# 06_ETHERNET.net
KiCad netlist of a schematic drawn in Altium Designer
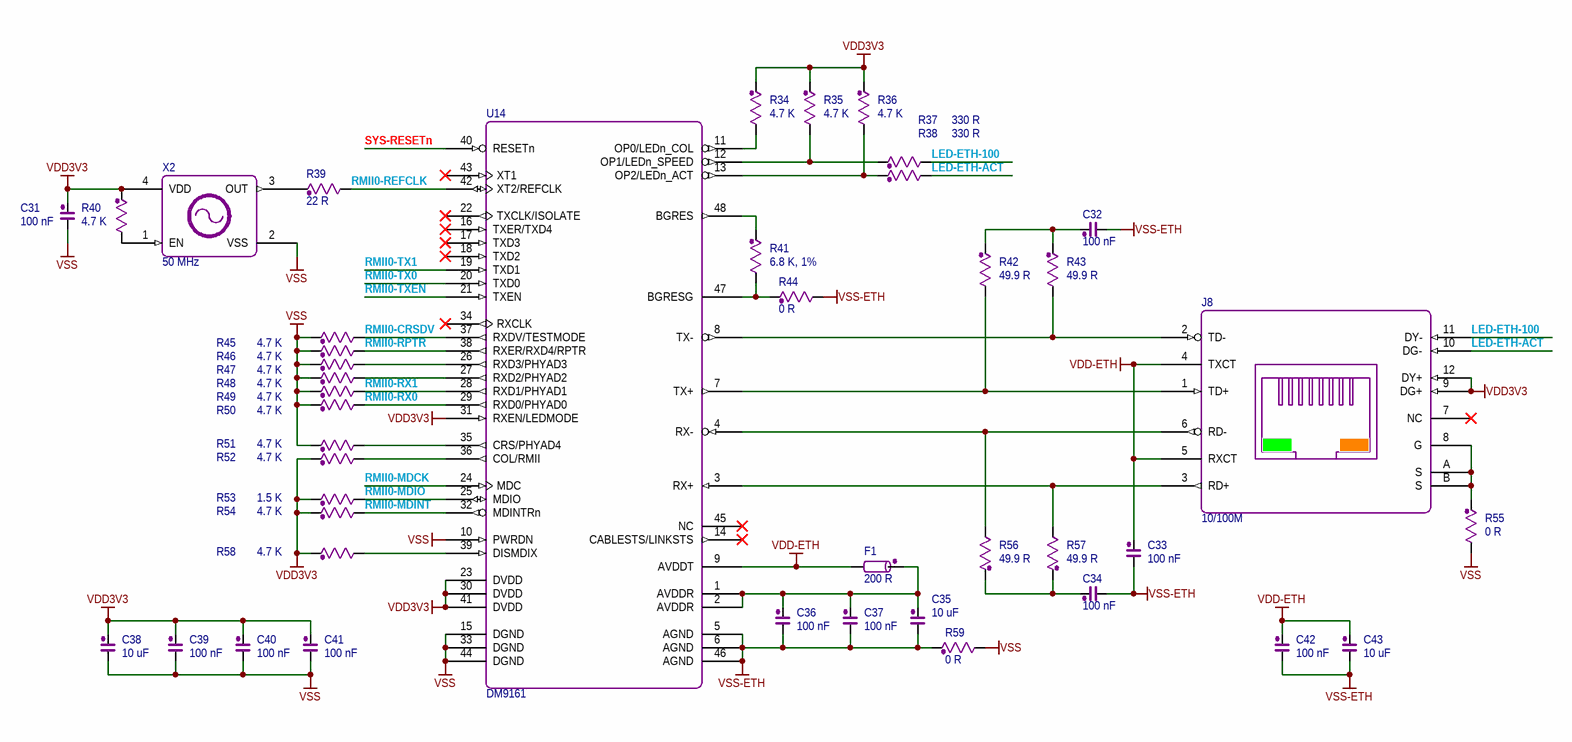
[diagram p0: 06_ETHERNET.SchDoc]

(export (version "E")
  (design (tool "Eeschema 10.0.6"))
  (components
    (comp (ref "C31")
      (value "100 nF")
      (footprint "0402A1")
      (description "Normal Capacitor")
      (fields
        (field (name "PARTNUMBER") "0")
        (field (name "PUBLISHER") "Cowin")
        (field (name "DESIGNER") "shyul")
      )
      (libsource (lib "Basc_1_Passive") (part "CAP"))
    )
    (comp (ref "C32")
      (value "100 nF")
      (footprint "0603A1")
      (description "Normal Capacitor")
      (fields
        (field (name "PARTNUMBER") "0")
        (field (name "PUBLISHER") "Cowin")
        (field (name "DESIGNER") "shyul")
      )
      (libsource (lib "") (part "CAP_1"))
    )
    (comp (ref "C33")
      (value "100 nF")
      (footprint "0603A1")
      (description "Normal Capacitor")
      (fields
        (field (name "PARTNUMBER") "0")
        (field (name "PUBLISHER") "Cowin")
        (field (name "DESIGNER") "shyul")
      )
      (libsource (lib "Basc_1_Passive") (part "CAP"))
    )
    (comp (ref "C34")
      (value "100 nF")
      (footprint "0603A1")
      (description "Normal Capacitor")
      (fields
        (field (name "PARTNUMBER") "0")
        (field (name "PUBLISHER") "Cowin")
        (field (name "DESIGNER") "shyul")
      )
      (libsource (lib "") (part "CAP_1"))
    )
    (comp (ref "C35")
      (value "10 uF")
      (footprint "0603A1")
      (description "Normal Capacitor")
      (fields
        (field (name "PARTNUMBER") "0")
        (field (name "PUBLISHER") "Cowin")
        (field (name "DESIGNER") "shyul")
      )
      (libsource (lib "Basc_1_Passive") (part "CAP"))
    )
    (comp (ref "C36")
      (value "100 nF")
      (footprint "0402A1")
      (description "Normal Capacitor")
      (fields
        (field (name "PARTNUMBER") "0")
        (field (name "PUBLISHER") "Cowin")
        (field (name "DESIGNER") "shyul")
      )
      (libsource (lib "Basc_1_Passive") (part "CAP"))
    )
    (comp (ref "C37")
      (value "100 nF")
      (footprint "0402A1")
      (description "Normal Capacitor")
      (fields
        (field (name "PARTNUMBER") "0")
        (field (name "PUBLISHER") "Cowin")
        (field (name "DESIGNER") "shyul")
      )
      (libsource (lib "Basc_1_Passive") (part "CAP"))
    )
    (comp (ref "C38")
      (value "10 uF")
      (footprint "0603A1")
      (description "Normal Capacitor")
      (fields
        (field (name "PARTNUMBER") "0")
        (field (name "PUBLISHER") "Cowin")
        (field (name "DESIGNER") "shyul")
      )
      (libsource (lib "Basc_1_Passive") (part "CAP"))
    )
    (comp (ref "C39")
      (value "100 nF")
      (footprint "0402A1")
      (description "Normal Capacitor")
      (fields
        (field (name "PARTNUMBER") "0")
        (field (name "PUBLISHER") "Cowin")
        (field (name "DESIGNER") "shyul")
      )
      (libsource (lib "Basc_1_Passive") (part "CAP"))
    )
    (comp (ref "C40")
      (value "100 nF")
      (footprint "0402A1")
      (description "Normal Capacitor")
      (fields
        (field (name "PARTNUMBER") "0")
        (field (name "PUBLISHER") "Cowin")
        (field (name "DESIGNER") "shyul")
      )
      (libsource (lib "Basc_1_Passive") (part "CAP"))
    )
    (comp (ref "C41")
      (value "100 nF")
      (footprint "0402A1")
      (description "Normal Capacitor")
      (fields
        (field (name "PARTNUMBER") "0")
        (field (name "PUBLISHER") "Cowin")
        (field (name "DESIGNER") "shyul")
      )
      (libsource (lib "Basc_1_Passive") (part "CAP"))
    )
    (comp (ref "C42")
      (value "100 nF")
      (footprint "0402A1")
      (description "Normal Capacitor")
      (fields
        (field (name "PARTNUMBER") "0")
        (field (name "PUBLISHER") "Cowin")
        (field (name "DESIGNER") "shyul")
      )
      (libsource (lib "Basc_1_Passive") (part "CAP"))
    )
    (comp (ref "C43")
      (value "10 uF")
      (footprint "0603A1")
      (description "Normal Capacitor")
      (fields
        (field (name "PARTNUMBER") "0")
        (field (name "PUBLISHER") "Cowin")
        (field (name "DESIGNER") "shyul")
      )
      (libsource (lib "Basc_1_Passive") (part "CAP"))
    )
    (comp (ref "F1")
      (value "200 R")
      (footprint "0603A3")
      (description "EMI Bead")
      (fields
        (field (name "PARTNUMBER") "BLM")
        (field (name "DESIGNER") "shyul")
        (field (name "PUBLISHER") "Cowin")
      )
      (libsource (lib "Basc_2_EMI_Protection") (part "BEAD"))
    )
    (comp (ref "J8")
      (value "10/100M")
      (footprint "RJ45_JACK_B")
      (description "RJ45 Pulse Jack with LED")
      (fields
        (field (name "PARTNUMBER") "J0011D21B")
        (field (name "PUBLISHER") "Cowin")
        (field (name "DESIGNER") "shyul")
      )
      (libsource (lib "Connector_1_General") (part "RJ45_JACK_B"))
    )
    (comp (ref "R34")
      (value "4.7 K")
      (footprint "0402A2")
      (description "Normal Resistor")
      (fields
        (field (name "PARTNUMBER") "0")
        (field (name "DESIGNER") "shyul")
        (field (name "PUBLISHER") "Cowin")
      )
      (libsource (lib "Basc_1_Passive") (part "RES"))
    )
    (comp (ref "R35")
      (value "4.7 K")
      (footprint "0402A2")
      (description "Normal Resistor")
      (fields
        (field (name "PARTNUMBER") "0")
        (field (name "DESIGNER") "shyul")
        (field (name "PUBLISHER") "Cowin")
      )
      (libsource (lib "Basc_1_Passive") (part "RES"))
    )
    (comp (ref "R36")
      (value "4.7 K")
      (footprint "0402A2")
      (description "Normal Resistor")
      (fields
        (field (name "PARTNUMBER") "0")
        (field (name "DESIGNER") "shyul")
        (field (name "PUBLISHER") "Cowin")
      )
      (libsource (lib "Basc_1_Passive") (part "RES"))
    )
    (comp (ref "R37")
      (value "330 R")
      (footprint "0402A2")
      (description "Normal Resistor")
      (fields
        (field (name "PARTNUMBER") "0")
        (field (name "DESIGNER") "shyul")
        (field (name "PUBLISHER") "Cowin")
      )
      (libsource (lib "Basc_1_Passive") (part "RES"))
    )
    (comp (ref "R38")
      (value "330 R")
      (footprint "0402A2")
      (description "Normal Resistor")
      (fields
        (field (name "PARTNUMBER") "0")
        (field (name "DESIGNER") "shyul")
        (field (name "PUBLISHER") "Cowin")
      )
      (libsource (lib "Basc_1_Passive") (part "RES"))
    )
    (comp (ref "R39")
      (value "22 R")
      (footprint "0402A2")
      (description "Normal Resistor")
      (fields
        (field (name "PARTNUMBER") "0")
        (field (name "DESIGNER") "shyul")
        (field (name "PUBLISHER") "Cowin")
      )
      (libsource (lib "Basc_1_Passive") (part "RES"))
    )
    (comp (ref "R40")
      (value "4.7 K")
      (footprint "0402A2")
      (description "Normal Resistor")
      (fields
        (field (name "PARTNUMBER") "0")
        (field (name "DESIGNER") "shyul")
        (field (name "PUBLISHER") "Cowin")
      )
      (libsource (lib "Basc_1_Passive") (part "RES"))
    )
    (comp (ref "R41")
      (value "6.8 K, 1%")
      (footprint "0603A2")
      (description "Normal Resistor")
      (fields
        (field (name "PARTNUMBER") "0")
        (field (name "DESIGNER") "shyul")
        (field (name "PUBLISHER") "Cowin")
      )
      (libsource (lib "Basc_1_Passive") (part "RES"))
    )
    (comp (ref "R42")
      (value "49.9 R")
      (footprint "0603A2")
      (description "Normal Resistor")
      (fields
        (field (name "PARTNUMBER") "0")
        (field (name "DESIGNER") "shyul")
        (field (name "PUBLISHER") "Cowin")
      )
      (libsource (lib "Basc_1_Passive") (part "RES"))
    )
    (comp (ref "R43")
      (value "49.9 R")
      (footprint "0603A2")
      (description "Normal Resistor")
      (fields
        (field (name "PARTNUMBER") "0")
        (field (name "DESIGNER") "shyul")
        (field (name "PUBLISHER") "Cowin")
      )
      (libsource (lib "Basc_1_Passive") (part "RES"))
    )
    (comp (ref "R44")
      (value "0 R")
      (footprint "0402A2")
      (description "Normal Resistor")
      (fields
        (field (name "PARTNUMBER") "0")
        (field (name "DESIGNER") "shyul")
        (field (name "PUBLISHER") "Cowin")
      )
      (libsource (lib "Basc_1_Passive") (part "RES"))
    )
    (comp (ref "R45")
      (value "4.7 K")
      (footprint "0402A2")
      (description "Normal Resistor")
      (fields
        (field (name "PARTNUMBER") "0")
        (field (name "DESIGNER") "shyul")
        (field (name "PUBLISHER") "Cowin")
      )
      (libsource (lib "Basc_1_Passive") (part "RES"))
    )
    (comp (ref "R46")
      (value "4.7 K")
      (footprint "0402A2")
      (description "Normal Resistor")
      (fields
        (field (name "PARTNUMBER") "0")
        (field (name "DESIGNER") "shyul")
        (field (name "PUBLISHER") "Cowin")
      )
      (libsource (lib "Basc_1_Passive") (part "RES"))
    )
    (comp (ref "R47")
      (value "4.7 K")
      (footprint "0402A2")
      (description "Normal Resistor")
      (fields
        (field (name "PARTNUMBER") "0")
        (field (name "DESIGNER") "shyul")
        (field (name "PUBLISHER") "Cowin")
      )
      (libsource (lib "Basc_1_Passive") (part "RES"))
    )
    (comp (ref "R48")
      (value "4.7 K")
      (footprint "0402A2")
      (description "Normal Resistor")
      (fields
        (field (name "PARTNUMBER") "0")
        (field (name "DESIGNER") "shyul")
        (field (name "PUBLISHER") "Cowin")
      )
      (libsource (lib "Basc_1_Passive") (part "RES"))
    )
    (comp (ref "R49")
      (value "4.7 K")
      (footprint "0402A2")
      (description "Normal Resistor")
      (fields
        (field (name "PARTNUMBER") "0")
        (field (name "DESIGNER") "shyul")
        (field (name "PUBLISHER") "Cowin")
      )
      (libsource (lib "Basc_1_Passive") (part "RES"))
    )
    (comp (ref "R50")
      (value "4.7 K")
      (footprint "0402A2")
      (description "Normal Resistor")
      (fields
        (field (name "PARTNUMBER") "0")
        (field (name "DESIGNER") "shyul")
        (field (name "PUBLISHER") "Cowin")
      )
      (libsource (lib "Basc_1_Passive") (part "RES"))
    )
    (comp (ref "R51")
      (value "4.7 K")
      (footprint "0402A2")
      (description "Normal Resistor")
      (fields
        (field (name "PARTNUMBER") "0")
        (field (name "DESIGNER") "shyul")
        (field (name "PUBLISHER") "Cowin")
      )
      (libsource (lib "Basc_1_Passive") (part "RES"))
    )
    (comp (ref "R52")
      (value "4.7 K")
      (footprint "0402A2")
      (description "Normal Resistor")
      (fields
        (field (name "PARTNUMBER") "0")
        (field (name "DESIGNER") "shyul")
        (field (name "PUBLISHER") "Cowin")
      )
      (libsource (lib "Basc_1_Passive") (part "RES"))
    )
    (comp (ref "R53")
      (value "1.5 K")
      (footprint "0402A2")
      (description "Normal Resistor")
      (fields
        (field (name "PARTNUMBER") "0")
        (field (name "DESIGNER") "shyul")
        (field (name "PUBLISHER") "Cowin")
      )
      (libsource (lib "Basc_1_Passive") (part "RES"))
    )
    (comp (ref "R54")
      (value "4.7 K")
      (footprint "0402A2")
      (description "Normal Resistor")
      (fields
        (field (name "PARTNUMBER") "0")
        (field (name "DESIGNER") "shyul")
        (field (name "PUBLISHER") "Cowin")
      )
      (libsource (lib "Basc_1_Passive") (part "RES"))
    )
    (comp (ref "R55")
      (value "0 R")
      (footprint "0603A2")
      (description "Normal Resistor")
      (fields
        (field (name "PARTNUMBER") "0")
        (field (name "DESIGNER") "shyul")
        (field (name "PUBLISHER") "Cowin")
      )
      (libsource (lib "Basc_1_Passive") (part "RES"))
    )
    (comp (ref "R56")
      (value "49.9 R")
      (footprint "0603A2")
      (description "Normal Resistor")
      (fields
        (field (name "PARTNUMBER") "0")
        (field (name "DESIGNER") "shyul")
        (field (name "PUBLISHER") "Cowin")
      )
      (libsource (lib "Basc_1_Passive") (part "RES"))
    )
    (comp (ref "R57")
      (value "49.9 R")
      (footprint "0603A2")
      (description "Normal Resistor")
      (fields
        (field (name "PARTNUMBER") "0")
        (field (name "DESIGNER") "shyul")
        (field (name "PUBLISHER") "Cowin")
      )
      (libsource (lib "Basc_1_Passive") (part "RES"))
    )
    (comp (ref "R58")
      (value "4.7 K")
      (footprint "0402A2")
      (description "Normal Resistor")
      (fields
        (field (name "PARTNUMBER") "0")
        (field (name "DESIGNER") "shyul")
        (field (name "PUBLISHER") "Cowin")
      )
      (libsource (lib "Basc_1_Passive") (part "RES"))
    )
    (comp (ref "R59")
      (value "0 R")
      (footprint "0603A2")
      (description "Normal Resistor")
      (fields
        (field (name "PARTNUMBER") "0")
        (field (name "DESIGNER") "shyul")
        (field (name "PUBLISHER") "Cowin")
      )
      (libsource (lib "Basc_1_Passive") (part "RES"))
    )
    (comp (ref "U14")
      (value "DM9161")
      (footprint "TQFP-48A")
      (description "DM9161 10/100M Ethernet PHY")
      (fields
        (field (name "PARTNUMBER") "DM9161AEP")
        (field (name "PUBLISHER") "Cowin")
        (field (name "DESIGNER") "shyul")
      )
      (libsource (lib "PCB_MDB-U01") (part "DM9161"))
    )
    (comp (ref "X2")
      (value "50 MHz")
      (footprint "OSC_4B_S_5032")
      (description "Crystal Oscillator")
      (fields
        (field (name "PARTNUMBER") "0")
        (field (name "PUBLISHER") "Cowin")
        (field (name "DESIGNER") "shyul")
      )
      (libsource (lib "Basc_4_Other") (part "OSC_4B"))
    )
  )
  (nets
    (net (code "1") (name "/LED-ETH-100") (class "Default")
      (node (ref "J8") (pin "11") (pinfunction "DY-_11") (pintype "input"))
      (node (ref "R37") (pin "1") (pinfunction "1_1") (pintype "passive"))
    )
    (net (code "2") (name "/LED-ETH-ACT") (class "Default")
      (node (ref "J8") (pin "10") (pinfunction "DG-_10") (pintype "input"))
      (node (ref "R38") (pin "1") (pinfunction "1_1") (pintype "passive"))
    )
    (net (code "3") (name "/RMII0-CRSDV") (class "Default")
      (node (ref "R45") (pin "1") (pinfunction "1_1") (pintype "passive"))
      (node (ref "U14") (pin "37") (pinfunction "RXDV/TESTMODE_37") (pintype "output"))
    )
    (net (code "4") (name "/RMII0-MDCK") (class "Default")
      (node (ref "U14") (pin "24") (pinfunction "MDC_24") (pintype "input"))
    )
    (net (code "5") (name "/RMII0-MDINT") (class "Default")
      (node (ref "R54") (pin "1") (pinfunction "1_1") (pintype "passive"))
      (node (ref "U14") (pin "32") (pinfunction "MDINTRn_32") (pintype "output"))
    )
    (net (code "6") (name "/RMII0-MDIO") (class "Default")
      (node (ref "R53") (pin "1") (pinfunction "1_1") (pintype "passive"))
      (node (ref "U14") (pin "25") (pinfunction "MDIO_25") (pintype "bidirectional"))
    )
    (net (code "7") (name "/RMII0-REFCLK") (class "Default")
      (node (ref "R39") (pin "1") (pinfunction "1_1") (pintype "passive"))
      (node (ref "U14") (pin "42") (pinfunction "XT2/REFCLK_42") (pintype "bidirectional"))
    )
    (net (code "8") (name "/RMII0-RPTR") (class "Default")
      (node (ref "R46") (pin "1") (pinfunction "1_1") (pintype "passive"))
      (node (ref "U14") (pin "38") (pinfunction "RXER/RXD4/RPTR_38") (pintype "output"))
    )
    (net (code "9") (name "/RMII0-RX0") (class "Default")
      (node (ref "R50") (pin "1") (pinfunction "1_1") (pintype "passive"))
      (node (ref "U14") (pin "29") (pinfunction "RXD0/PHYAD0_29") (pintype "output"))
    )
    (net (code "10") (name "/RMII0-RX1") (class "Default")
      (node (ref "R49") (pin "1") (pinfunction "1_1") (pintype "passive"))
      (node (ref "U14") (pin "28") (pinfunction "RXD1/PHYAD1_28") (pintype "output"))
    )
    (net (code "11") (name "/RMII0-TX0") (class "Default")
      (node (ref "U14") (pin "20") (pinfunction "TXD0_20") (pintype "input"))
    )
    (net (code "12") (name "/RMII0-TX1") (class "Default")
      (node (ref "U14") (pin "19") (pinfunction "TXD1_19") (pintype "input"))
    )
    (net (code "13") (name "/RMII0-TXEN") (class "Default")
      (node (ref "U14") (pin "21") (pinfunction "TXEN_21") (pintype "input"))
    )
    (net (code "14") (name "/SYS-RESETn") (class "Default")
      (node (ref "U14") (pin "40") (pinfunction "RESETn_40") (pintype "input"))
    )
    (net (code "15") (name "Net-(C32-Pad2)") (class "Default")
      (node (ref "C32") (pin "2") (pinfunction "2_2") (pintype "passive"))
      (node (ref "R42") (pin "2") (pinfunction "2_2") (pintype "passive"))
      (node (ref "R43") (pin "2") (pinfunction "2_2") (pintype "passive"))
    )
    (net (code "16") (name "Net-(C34-Pad2)") (class "Default")
      (node (ref "C34") (pin "2") (pinfunction "2_2") (pintype "passive"))
      (node (ref "R56") (pin "2") (pinfunction "2_2") (pintype "passive"))
      (node (ref "R57") (pin "2") (pinfunction "2_2") (pintype "passive"))
    )
    (net (code "17") (name "Net-(C35-Pad2)") (class "Default")
      (node (ref "C35") (pin "2") (pinfunction "2_2") (pintype "passive"))
      (node (ref "C36") (pin "2") (pinfunction "2_2") (pintype "passive"))
      (node (ref "C37") (pin "2") (pinfunction "2_2") (pintype "passive"))
      (node (ref "F1") (pin "2") (pinfunction "2_2") (pintype "passive"))
      (node (ref "U14") (pin "1") (pinfunction "AVDDR_1") (pintype "passive"))
      (node (ref "U14") (pin "2") (pinfunction "AVDDR_2") (pintype "passive"))
    )
    (net (code "18") (name "Net-(J8-G)") (class "Default")
      (node (ref "J8") (pin "8") (pinfunction "G_8") (pintype "passive"))
      (node (ref "J8") (pin "A") (pinfunction "S_A") (pintype "passive"))
      (node (ref "J8") (pin "B") (pinfunction "S_B") (pintype "passive"))
      (node (ref "R55") (pin "2") (pinfunction "2_2") (pintype "passive"))
    )
    (net (code "19") (name "Net-(J8-RD+)") (class "Default")
      (node (ref "J8") (pin "3") (pinfunction "RD+_3") (pintype "output"))
      (node (ref "R57") (pin "1") (pinfunction "1_1") (pintype "passive"))
      (node (ref "U14") (pin "3") (pinfunction "RX+_3") (pintype "input"))
    )
    (net (code "20") (name "Net-(J8-RD-)") (class "Default")
      (node (ref "J8") (pin "6") (pinfunction "RD-_6") (pintype "output"))
      (node (ref "R56") (pin "1") (pinfunction "1_1") (pintype "passive"))
      (node (ref "U14") (pin "4") (pinfunction "RX-_4") (pintype "input"))
    )
    (net (code "21") (name "Net-(J8-TD+)") (class "Default")
      (node (ref "J8") (pin "1") (pinfunction "TD+_1") (pintype "input"))
      (node (ref "R42") (pin "1") (pinfunction "1_1") (pintype "passive"))
      (node (ref "U14") (pin "7") (pinfunction "TX+_7") (pintype "output"))
    )
    (net (code "22") (name "Net-(J8-TD-)") (class "Default")
      (node (ref "J8") (pin "2") (pinfunction "TD-_2") (pintype "input"))
      (node (ref "R43") (pin "1") (pinfunction "1_1") (pintype "passive"))
      (node (ref "U14") (pin "8") (pinfunction "TX-_8") (pintype "output"))
    )
    (net (code "23") (name "Net-(U14-BGRES)") (class "Default")
      (node (ref "R41") (pin "2") (pinfunction "2_2") (pintype "passive"))
      (node (ref "U14") (pin "48") (pinfunction "BGRES_48") (pintype "output"))
    )
    (net (code "24") (name "Net-(U14-BGRESG)") (class "Default")
      (node (ref "R41") (pin "1") (pinfunction "1_1") (pintype "passive"))
      (node (ref "R44") (pin "2") (pinfunction "2_2") (pintype "passive"))
      (node (ref "U14") (pin "47") (pinfunction "BGRESG_47") (pintype "passive"))
    )
    (net (code "25") (name "Net-(U14-COL{slash}RMII)") (class "Default")
      (node (ref "R52") (pin "1") (pinfunction "1_1") (pintype "passive"))
      (node (ref "U14") (pin "36") (pinfunction "COL/RMII_36") (pintype "output"))
    )
    (net (code "26") (name "Net-(U14-CRS{slash}PHYAD4)") (class "Default")
      (node (ref "R51") (pin "1") (pinfunction "1_1") (pintype "passive"))
      (node (ref "U14") (pin "35") (pinfunction "CRS/PHYAD4_35") (pintype "output"))
    )
    (net (code "27") (name "Net-(U14-DISMDIX)") (class "Default")
      (node (ref "R58") (pin "1") (pinfunction "1_1") (pintype "passive"))
      (node (ref "U14") (pin "39") (pinfunction "DISMDIX_39") (pintype "input"))
    )
    (net (code "28") (name "Net-(U14-OP0{slash}LEDn_COL)") (class "Default")
      (node (ref "R34") (pin "1") (pinfunction "1_1") (pintype "passive"))
      (node (ref "U14") (pin "11") (pinfunction "OP0/LEDn_COL_11") (pintype "output"))
    )
    (net (code "29") (name "Net-(U14-OP1{slash}LEDn_SPEED)") (class "Default")
      (node (ref "R35") (pin "1") (pinfunction "1_1") (pintype "passive"))
      (node (ref "R37") (pin "2") (pinfunction "2_2") (pintype "passive"))
      (node (ref "U14") (pin "12") (pinfunction "OP1/LEDn_SPEED_12") (pintype "output"))
    )
    (net (code "30") (name "Net-(U14-OP2{slash}LEDn_ACT)") (class "Default")
      (node (ref "R36") (pin "1") (pinfunction "1_1") (pintype "passive"))
      (node (ref "R38") (pin "2") (pinfunction "2_2") (pintype "passive"))
      (node (ref "U14") (pin "13") (pinfunction "OP2/LEDn_ACT_13") (pintype "output"))
    )
    (net (code "31") (name "Net-(U14-RXD2{slash}PHYAD2)") (class "Default")
      (node (ref "R48") (pin "1") (pinfunction "1_1") (pintype "passive"))
      (node (ref "U14") (pin "27") (pinfunction "RXD2/PHYAD2_27") (pintype "output"))
    )
    (net (code "32") (name "Net-(U14-RXD3{slash}PHYAD3)") (class "Default")
      (node (ref "R47") (pin "1") (pinfunction "1_1") (pintype "passive"))
      (node (ref "U14") (pin "26") (pinfunction "RXD3/PHYAD3_26") (pintype "output"))
    )
    (net (code "33") (name "Net-(X2-EN)") (class "Default")
      (node (ref "R40") (pin "1") (pinfunction "1_1") (pintype "passive"))
      (node (ref "X2") (pin "1") (pinfunction "EN_1") (pintype "input"))
    )
    (net (code "34") (name "Net-(X2-OUT)") (class "Default")
      (node (ref "R39") (pin "2") (pinfunction "2_2") (pintype "passive"))
      (node (ref "X2") (pin "3") (pinfunction "OUT_3") (pintype "output"))
    )
    (net (code "35") (name "VDD-ETH") (class "Default")
      (node (ref "C33") (pin "2") (pinfunction "2_2") (pintype "passive"))
      (node (ref "C42") (pin "2") (pinfunction "2_2") (pintype "passive"))
      (node (ref "C43") (pin "2") (pinfunction "2_2") (pintype "passive"))
      (node (ref "F1") (pin "1") (pinfunction "1_1") (pintype "passive"))
      (node (ref "J8") (pin "4") (pinfunction "TXCT_4") (pintype "passive"))
      (node (ref "J8") (pin "5") (pinfunction "RXCT_5") (pintype "passive"))
      (node (ref "U14") (pin "9") (pinfunction "AVDDT_9") (pintype "passive"))
    )
    (net (code "36") (name "VDD3V3") (class "Default")
      (node (ref "C31") (pin "2") (pinfunction "2_2") (pintype "passive"))
      (node (ref "C38") (pin "2") (pinfunction "2_2") (pintype "passive"))
      (node (ref "C39") (pin "2") (pinfunction "2_2") (pintype "passive"))
      (node (ref "C40") (pin "2") (pinfunction "2_2") (pintype "passive"))
      (node (ref "C41") (pin "2") (pinfunction "2_2") (pintype "passive"))
      (node (ref "J8") (pin "12") (pinfunction "DY+_12") (pintype "input"))
      (node (ref "J8") (pin "9") (pinfunction "DG+_9") (pintype "input"))
      (node (ref "R34") (pin "2") (pinfunction "2_2") (pintype "passive"))
      (node (ref "R35") (pin "2") (pinfunction "2_2") (pintype "passive"))
      (node (ref "R36") (pin "2") (pinfunction "2_2") (pintype "passive"))
      (node (ref "R40") (pin "2") (pinfunction "2_2") (pintype "passive"))
      (node (ref "R52") (pin "2") (pinfunction "2_2") (pintype "passive"))
      (node (ref "R53") (pin "2") (pinfunction "2_2") (pintype "passive"))
      (node (ref "R54") (pin "2") (pinfunction "2_2") (pintype "passive"))
      (node (ref "R58") (pin "2") (pinfunction "2_2") (pintype "passive"))
      (node (ref "U14") (pin "23") (pinfunction "DVDD_23") (pintype "passive"))
      (node (ref "U14") (pin "30") (pinfunction "DVDD_30") (pintype "passive"))
      (node (ref "U14") (pin "31") (pinfunction "RXEN/LEDMODE_31") (pintype "input"))
      (node (ref "U14") (pin "41") (pinfunction "DVDD_41") (pintype "passive"))
      (node (ref "X2") (pin "4") (pinfunction "VDD_4") (pintype "power_in"))
    )
    (net (code "37") (name "VSS") (class "Default")
      (node (ref "C31") (pin "1") (pinfunction "1_1") (pintype "passive"))
      (node (ref "C38") (pin "1") (pinfunction "1_1") (pintype "passive"))
      (node (ref "C39") (pin "1") (pinfunction "1_1") (pintype "passive"))
      (node (ref "C40") (pin "1") (pinfunction "1_1") (pintype "passive"))
      (node (ref "C41") (pin "1") (pinfunction "1_1") (pintype "passive"))
      (node (ref "R45") (pin "2") (pinfunction "2_2") (pintype "passive"))
      (node (ref "R46") (pin "2") (pinfunction "2_2") (pintype "passive"))
      (node (ref "R47") (pin "2") (pinfunction "2_2") (pintype "passive"))
      (node (ref "R48") (pin "2") (pinfunction "2_2") (pintype "passive"))
      (node (ref "R49") (pin "2") (pinfunction "2_2") (pintype "passive"))
      (node (ref "R50") (pin "2") (pinfunction "2_2") (pintype "passive"))
      (node (ref "R51") (pin "2") (pinfunction "2_2") (pintype "passive"))
      (node (ref "R55") (pin "1") (pinfunction "1_1") (pintype "passive"))
      (node (ref "R59") (pin "1") (pinfunction "1_1") (pintype "passive"))
      (node (ref "U14") (pin "10") (pinfunction "PWRDN_10") (pintype "input"))
      (node (ref "U14") (pin "15") (pinfunction "DGND_15") (pintype "passive"))
      (node (ref "U14") (pin "33") (pinfunction "DGND_33") (pintype "passive"))
      (node (ref "U14") (pin "44") (pinfunction "DGND_44") (pintype "passive"))
      (node (ref "X2") (pin "2") (pinfunction "VSS_2") (pintype "power_in"))
    )
    (net (code "38") (name "VSS-ETH") (class "Default")
      (node (ref "C32") (pin "1") (pinfunction "1_1") (pintype "passive"))
      (node (ref "C33") (pin "1") (pinfunction "1_1") (pintype "passive"))
      (node (ref "C34") (pin "1") (pinfunction "1_1") (pintype "passive"))
      (node (ref "C35") (pin "1") (pinfunction "1_1") (pintype "passive"))
      (node (ref "C36") (pin "1") (pinfunction "1_1") (pintype "passive"))
      (node (ref "C37") (pin "1") (pinfunction "1_1") (pintype "passive"))
      (node (ref "C42") (pin "1") (pinfunction "1_1") (pintype "passive"))
      (node (ref "C43") (pin "1") (pinfunction "1_1") (pintype "passive"))
      (node (ref "R44") (pin "1") (pinfunction "1_1") (pintype "passive"))
      (node (ref "R59") (pin "2") (pinfunction "2_2") (pintype "passive"))
      (node (ref "U14") (pin "46") (pinfunction "AGND_46") (pintype "passive"))
      (node (ref "U14") (pin "5") (pinfunction "AGND_5") (pintype "passive"))
      (node (ref "U14") (pin "6") (pinfunction "AGND_6") (pintype "passive"))
    )
    (net (code "39") (name "unconnected-(J8-NC-Pad7)") (class "Default")
      (node (ref "J8") (pin "7") (pinfunction "NC_7") (pintype "passive+no_connect"))
    )
    (net (code "40") (name "unconnected-(U14-CABLESTS{slash}LINKSTS-Pad14)") (class "Default")
      (node (ref "U14") (pin "14") (pinfunction "CABLESTS/LINKSTS_14") (pintype "output+no_connect"))
    )
    (net (code "41") (name "unconnected-(U14-NC-Pad45)") (class "Default")
      (node (ref "U14") (pin "45") (pinfunction "NC_45") (pintype "passive+no_connect"))
    )
    (net (code "42") (name "unconnected-(U14-RXCLK-Pad34)") (class "Default")
      (node (ref "U14") (pin "34") (pinfunction "RXCLK_34") (pintype "output+no_connect"))
    )
    (net (code "43") (name "unconnected-(U14-TXCLK{slash}ISOLATE-Pad22)") (class "Default")
      (node (ref "U14") (pin "22") (pinfunction "TXCLK/ISOLATE_22") (pintype "output+no_connect"))
    )
    (net (code "44") (name "unconnected-(U14-TXD2-Pad18)") (class "Default")
      (node (ref "U14") (pin "18") (pinfunction "TXD2_18") (pintype "input+no_connect"))
    )
    (net (code "45") (name "unconnected-(U14-TXD3-Pad17)") (class "Default")
      (node (ref "U14") (pin "17") (pinfunction "TXD3_17") (pintype "input+no_connect"))
    )
    (net (code "46") (name "unconnected-(U14-TXER{slash}TXD4-Pad16)") (class "Default")
      (node (ref "U14") (pin "16") (pinfunction "TXER/TXD4_16") (pintype "input+no_connect"))
    )
    (net (code "47") (name "unconnected-(U14-XT1-Pad43)") (class "Default")
      (node (ref "U14") (pin "43") (pinfunction "XT1_43") (pintype "input+no_connect"))
    )
  )
)
